# MCU.net
KiCad netlist of a schematic drawn in Altium Designer
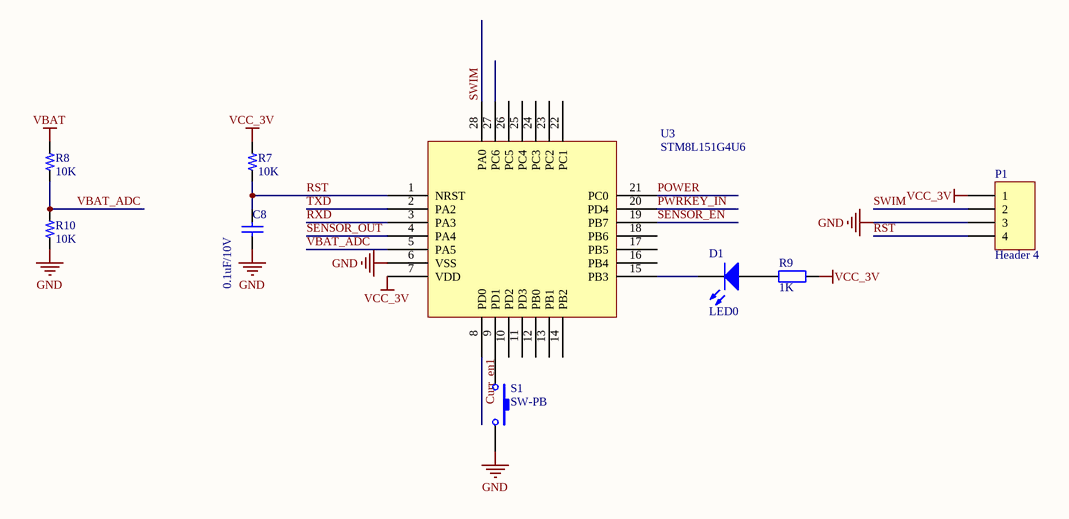
[diagram p0: MCU.SchDoc]

(export (version "E")
  (design (tool "Eeschema 10.0.6"))
  (components
    (comp (ref "C8")
      (value "0.1uF/10V")
      (footprint "0603C")
      (description "Capacitor")
      (fields (field (name "PUBLISHER") "Altium Limited"))
      (libsource (lib "Miscellaneous Devices") (part "Cap"))
    )
    (comp (ref "D1")
      (value "LED0")
      (footprint "0603LED")
      (description "Typical INFRARED GaAs LED")
      (fields (field (name "PUBLISHER") "Altium Limited"))
      (libsource (lib "Miscellaneous Devices") (part "LED0"))
    )
    (comp (ref "P1")
      (value "Header 4")
      (footprint "HDR1X4")
      (description "Header, 4-Pin")
      (fields (field (name "PUBLISHER") "Altium Limited"))
      (libsource (lib "Miscellaneous Connectors") (part "Header 4"))
    )
    (comp (ref "R7") (value "10K") (footprint "0603R") (description "R") (libsource (lib "JRJ_1") (part "R")))
    (comp (ref "R8") (value "10K") (footprint "0603R") (description "R") (libsource (lib "JRJ_1") (part "R")))
    (comp (ref "R9")
      (value "1K")
      (footprint "0603R")
      (description "Resistor")
      (fields (field (name "PUBLISHER") "Altium Limited"))
      (libsource (lib "Miscellaneous Devices") (part "Res2"))
    )
    (comp (ref "R10")
      (value "10K")
      (footprint "0603R")
      (description "R")
      (libsource (lib "JRJ_1") (part "R"))
    )
    (comp (ref "S1")
      (value "SW-PB")
      (footprint "key")
      (description "Switch")
      (fields (field (name "PUBLISHER") "Altium Limited"))
      (libsource (lib "Miscellaneous Devices") (part "SW-PB"))
    )
    (comp (ref "U3")
      (value "STM8L151G4U6")
      (footprint "UFQFPN28")
      (libsource (lib "Schlib_20110825") (part "STM8L151G4U6"))
    )
  )
  (nets
    (net (code "1") (name "/Curr_en1") (class "Default")
      (node (ref "U3") (pin "8") (pinfunction "PD0_8") (pintype "passive"))
    )
    (net (code "2") (name "/POWER") (class "Default")
      (node (ref "U3") (pin "21") (pinfunction "PC0_21") (pintype "passive"))
    )
    (net (code "3") (name "/PWRKEY_IN") (class "Default")
      (node (ref "U3") (pin "20") (pinfunction "PD4_20") (pintype "passive"))
    )
    (net (code "4") (name "/RST") (class "Default")
      (node (ref "C8") (pin "1") (pinfunction "1_1") (pintype "passive"))
      (node (ref "P1") (pin "4") (pinfunction "4_4") (pintype "passive"))
      (node (ref "R7") (pin "1") (pintype "passive"))
      (node (ref "U3") (pin "1") (pinfunction "NRST_1") (pintype "passive"))
    )
    (net (code "5") (name "/RXD") (class "Default")
      (node (ref "U3") (pin "3") (pinfunction "PA3_3") (pintype "passive"))
    )
    (net (code "6") (name "/SENSOR_EN") (class "Default")
      (node (ref "U3") (pin "19") (pinfunction "PB7_19") (pintype "passive"))
    )
    (net (code "7") (name "/SENSOR_OUT") (class "Default")
      (node (ref "U3") (pin "4") (pinfunction "PA4_4") (pintype "passive"))
    )
    (net (code "8") (name "/SWIM") (class "Default")
      (node (ref "P1") (pin "2") (pinfunction "2_2") (pintype "passive"))
      (node (ref "U3") (pin "28") (pinfunction "PA0_28") (pintype "passive"))
    )
    (net (code "9") (name "/TXD") (class "Default")
      (node (ref "U3") (pin "2") (pinfunction "PA2_2") (pintype "passive"))
    )
    (net (code "10") (name "/VBAT_ADC") (class "Default")
      (node (ref "R10") (pin "2") (pintype "passive"))
      (node (ref "R8") (pin "1") (pintype "passive"))
      (node (ref "U3") (pin "5") (pinfunction "PA5_5") (pintype "passive"))
    )
    (net (code "11") (name "GND") (class "Default")
      (node (ref "C8") (pin "2") (pinfunction "2_2") (pintype "passive"))
      (node (ref "P1") (pin "3") (pinfunction "3_3") (pintype "passive"))
      (node (ref "R10") (pin "1") (pintype "passive"))
      (node (ref "S1") (pin "2") (pinfunction "2_2") (pintype "passive"))
      (node (ref "U3") (pin "6") (pinfunction "VSS_6") (pintype "passive"))
    )
    (net (code "12") (name "Net-(D1-A)") (class "Default")
      (node (ref "D1") (pin "1") (pinfunction "A_1") (pintype "passive"))
      (node (ref "R9") (pin "2") (pinfunction "2_2") (pintype "passive"))
    )
    (net (code "13") (name "Net-(D1-K)") (class "Default")
      (node (ref "D1") (pin "2") (pinfunction "K_2") (pintype "passive"))
      (node (ref "U3") (pin "15") (pinfunction "PB3_15") (pintype "passive"))
    )
    (net (code "14") (name "Net-(U3-PD1)") (class "Default")
      (node (ref "S1") (pin "1") (pinfunction "1_1") (pintype "passive"))
      (node (ref "U3") (pin "9") (pinfunction "PD1_9") (pintype "passive"))
    )
    (net (code "15") (name "VBAT") (class "Default") (node (ref "R8") (pin "2") (pintype "passive")))
    (net (code "16") (name "VCC_3V") (class "Default")
      (node (ref "P1") (pin "1") (pinfunction "1_1") (pintype "passive"))
      (node (ref "R7") (pin "2") (pintype "passive"))
      (node (ref "R9") (pin "1") (pinfunction "1_1") (pintype "passive"))
      (node (ref "U3") (pin "7") (pinfunction "VDD_7") (pintype "passive"))
    )
    (net (code "17") (name "unconnected-(U3-PB0-Pad12)") (class "Default")
      (node (ref "U3") (pin "12") (pinfunction "PB0_12") (pintype "passive"))
    )
    (net (code "18") (name "unconnected-(U3-PB1-Pad13)") (class "Default")
      (node (ref "U3") (pin "13") (pinfunction "PB1_13") (pintype "passive"))
    )
    (net (code "19") (name "unconnected-(U3-PB2-Pad14)") (class "Default")
      (node (ref "U3") (pin "14") (pinfunction "PB2_14") (pintype "passive"))
    )
    (net (code "20") (name "unconnected-(U3-PB4-Pad16)") (class "Default")
      (node (ref "U3") (pin "16") (pinfunction "PB4_16") (pintype "passive"))
    )
    (net (code "21") (name "unconnected-(U3-PB5-Pad17)") (class "Default")
      (node (ref "U3") (pin "17") (pinfunction "PB5_17") (pintype "passive"))
    )
    (net (code "22") (name "unconnected-(U3-PB6-Pad18)") (class "Default")
      (node (ref "U3") (pin "18") (pinfunction "PB6_18") (pintype "passive"))
    )
    (net (code "23") (name "unconnected-(U3-PC1-Pad22)") (class "Default")
      (node (ref "U3") (pin "22") (pinfunction "PC1_22") (pintype "passive"))
    )
    (net (code "24") (name "unconnected-(U3-PC2-Pad23)") (class "Default")
      (node (ref "U3") (pin "23") (pinfunction "PC2_23") (pintype "passive"))
    )
    (net (code "25") (name "unconnected-(U3-PC3-Pad24)") (class "Default")
      (node (ref "U3") (pin "24") (pinfunction "PC3_24") (pintype "passive"))
    )
    (net (code "26") (name "unconnected-(U3-PC4-Pad25)") (class "Default")
      (node (ref "U3") (pin "25") (pinfunction "PC4_25") (pintype "passive"))
    )
    (net (code "27") (name "unconnected-(U3-PC5-Pad26)") (class "Default")
      (node (ref "U3") (pin "26") (pinfunction "PC5_26") (pintype "passive"))
    )
    (net (code "28") (name "unconnected-(U3-PC6-Pad27)") (class "Default")
      (node (ref "U3") (pin "27") (pinfunction "PC6_27") (pintype "passive"))
    )
    (net (code "29") (name "unconnected-(U3-PD2-Pad10)") (class "Default")
      (node (ref "U3") (pin "10") (pinfunction "PD2_10") (pintype "passive"))
    )
    (net (code "30") (name "unconnected-(U3-PD3-Pad11)") (class "Default")
      (node (ref "U3") (pin "11") (pinfunction "PD3_11") (pintype "passive"))
    )
  )
)
